# Smart_Homes.net
KiCad netlist of a schematic drawn in Altium Designer
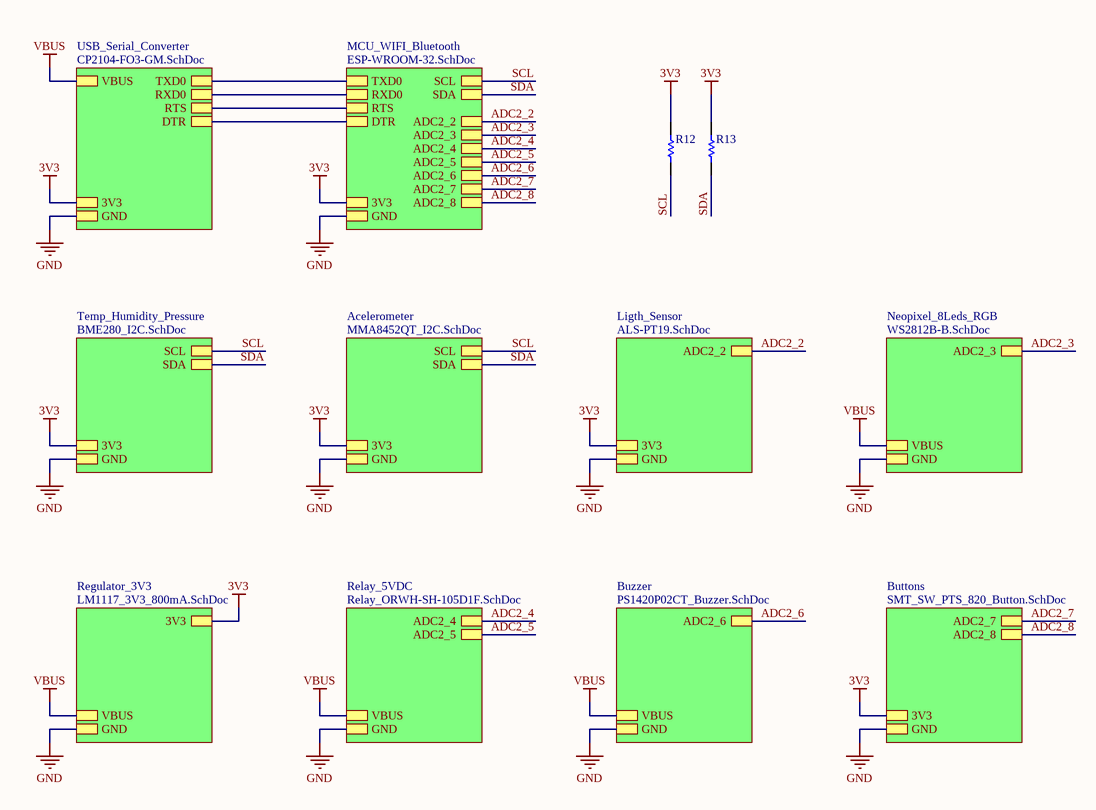
[diagram p0: Smart_Homes.SchDoc]

(export (version "E")
  (design (tool "Eeschema 10.0.6"))
  (components
    (comp (ref "R12")
      (value "RK73B2ATTD103J")
      (footprint "RESC2013X60X30NL20T20")
      (fields (field (name "MANUFACTURER") "KOA Speer"))
      (libsource (lib "Altium Content Vault") (part "RES"))
    )
    (comp (ref "R13")
      (value "RK73B2ATTD103J")
      (footprint "RESC2013X60X30NL20T20")
      (fields (field (name "MANUFACTURER") "KOA Speer"))
      (libsource (lib "Altium Content Vault") (part "RES"))
    )
  )
  (nets
    (net (code "11") (name "/SCL") (class "Default")
      (node (ref "R12") (pin "1") (pinfunction "1_1") (pintype "passive"))
    )
    (net (code "12") (name "/SDA") (class "Default")
      (node (ref "R13") (pin "1") (pinfunction "1_1") (pintype "passive"))
    )
    (net (code "14") (name "3V3") (class "Default")
      (node (ref "R12") (pin "2") (pinfunction "2_2") (pintype "passive"))
      (node (ref "R13") (pin "2") (pinfunction "2_2") (pintype "passive"))
    )
  )
)
